# max30208-breakout.net
KiCad netlist of a schematic drawn in EAGLE
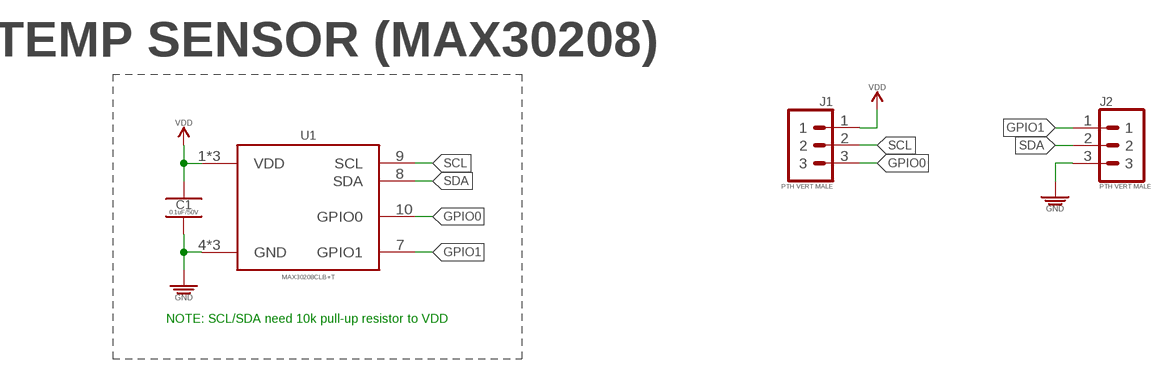
[diagram p0: schematic, sheet 1]

(export (version "E")
  (design (tool "Eeschema 10.0.6"))
  (components
    (comp (ref "C1")
      (value "0.1uF/50V")
      (footprint "eagle-import:CAPC1005X55_SMD-0402")
      (fields (field (name "MFR") "TDK Corporation") (field (name "MPN") "C1005X7R1H104K050BE"))
      (libsource (lib "eagle-import") (part "0.1UF_SMD-0402_50V-10%"))
    )
    (comp (ref "J1")
      (value "PTH VERT MALE")
      (footprint "eagle-import:HDRV3W64P254_1X3_762X254X838B")
      (fields (field (name "MFR") "Sullins Connector Solutions") (field (name "MPN") "PEC03SAAN"))
      (libsource (lib "eagle-import") (part "1X03_PTH_VERT_MALE_2.54MM"))
    )
    (comp (ref "J2")
      (value "PTH VERT MALE")
      (footprint "eagle-import:HDRV3W64P254_1X3_762X254X838B")
      (fields (field (name "MFR") "Sullins Connector Solutions") (field (name "MPN") "PEC03SAAN"))
      (libsource (lib "eagle-import") (part "1X03_PTH_VERT_MALE_2.54MM"))
    )
    (comp (ref "U1")
      (value "MAX30208CLB+T")
      (footprint "eagle-import:SON65P200X200X85-6N")
      (fields (field (name "MFR") "Maxim Integrated"))
      (libsource (lib "eagle-import") (part "MAX30208"))
    )
  )
  (nets
    (net (code "1") (name "GND") (class "Default")
      (node (ref "C1") (pin "2") (pinfunction "2_2") (pintype "passive"))
      (node (ref "J2") (pin "3") (pinfunction "3_3") (pintype "passive"))
      (node (ref "U1") (pin "4") (pinfunction "GND_4") (pintype "power_in"))
      (node (ref "U1") (pin "5") (pinfunction "GND_5") (pintype "power_in"))
      (node (ref "U1") (pin "6") (pinfunction "GND_6") (pintype "power_in"))
    )
    (net (code "2") (name "GPIO0") (class "Default")
      (node (ref "J1") (pin "3") (pinfunction "3_3") (pintype "passive"))
      (node (ref "U1") (pin "10") (pinfunction "GPIO0_10") (pintype "bidirectional"))
    )
    (net (code "3") (name "GPIO1") (class "Default")
      (node (ref "J2") (pin "1") (pinfunction "1_1") (pintype "passive"))
      (node (ref "U1") (pin "7") (pinfunction "GPIO1_7") (pintype "bidirectional"))
    )
    (net (code "4") (name "SCL") (class "Default")
      (node (ref "J1") (pin "2") (pinfunction "2_2") (pintype "passive"))
      (node (ref "U1") (pin "9") (pinfunction "SCL_9") (pintype "bidirectional"))
    )
    (net (code "5") (name "SDA") (class "Default")
      (node (ref "J2") (pin "2") (pinfunction "2_2") (pintype "passive"))
      (node (ref "U1") (pin "8") (pinfunction "SDA_8") (pintype "bidirectional"))
    )
    (net (code "6") (name "VDD") (class "Default")
      (node (ref "C1") (pin "1") (pinfunction "1_1") (pintype "passive"))
      (node (ref "J1") (pin "1") (pinfunction "1_1") (pintype "passive"))
      (node (ref "U1") (pin "1") (pinfunction "VDD_1") (pintype "power_in"))
      (node (ref "U1") (pin "2") (pinfunction "VDD_2") (pintype "power_in"))
      (node (ref "U1") (pin "3") (pinfunction "VDD_3") (pintype "power_in"))
    )
  )
)
